# L6205PD-Dual-Breakout-Board-B_00_02.net
KiCad netlist of a schematic drawn in EasyEDA
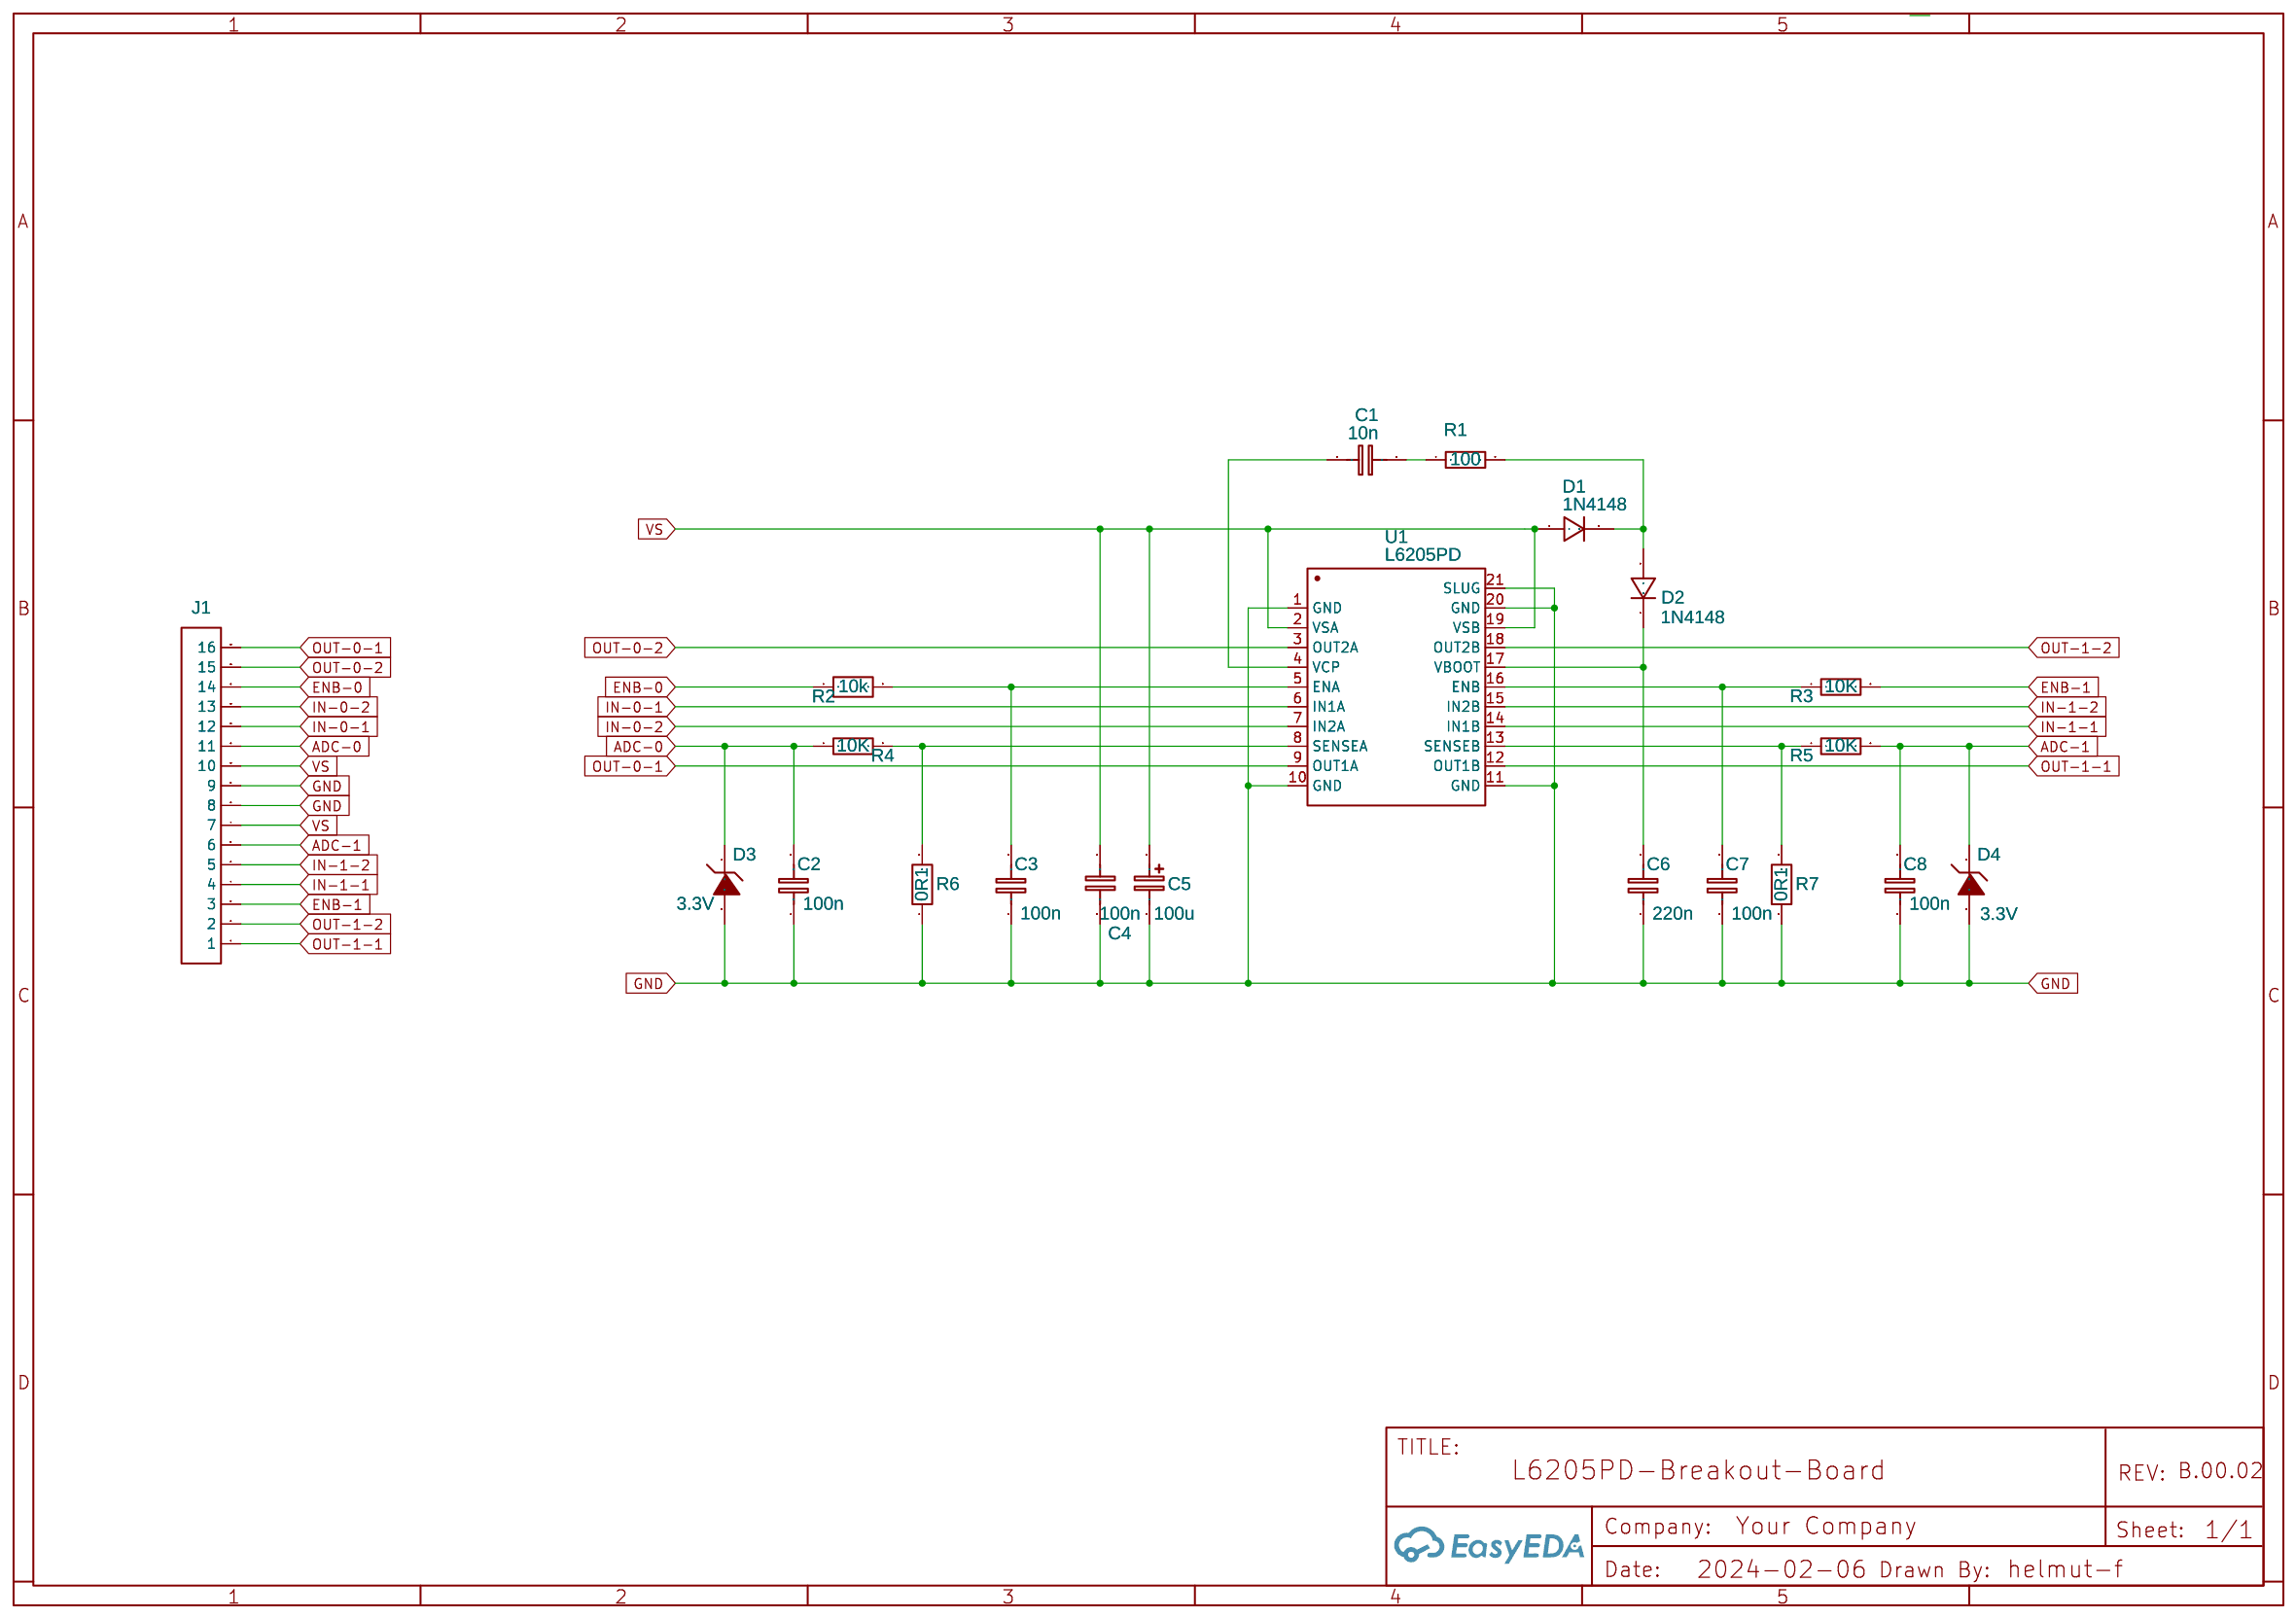
[diagram p0: schematic sheet]

(export (version "E")
  (design (tool "Eeschema 10.0.6"))
  (components
    (comp (ref "C1") (value "10n") (libsource (lib "") (part "C_0603_EU_3")))
    (comp (ref "C2") (value "100n") (libsource (lib "") (part "C_0603_EU")))
    (comp (ref "C3") (value "100n") (libsource (lib "") (part "C_0603_EU_1")))
    (comp (ref "C4") (value "100n") (libsource (lib "") (part "C_0603_EU_2")))
    (comp (ref "C5") (value "100u") (libsource (lib "") (part "CE_SMD_D5.0×H5.5_EU")))
    (comp (ref "C6") (value "220n") (libsource (lib "") (part "C_0603_EU_1")))
    (comp (ref "C7") (value "100n") (libsource (lib "") (part "C_0603_EU_1")))
    (comp (ref "C8") (value "100n") (libsource (lib "") (part "C_0603_EU_1")))
    (comp (ref "D1")
      (value "1N4148")
      (fields (field (name "Manufacturer") "SEMTECH"))
      (libsource (lib "") (part "1N4148"))
    )
    (comp (ref "D2")
      (value "1N4148")
      (fields (field (name "Manufacturer") "SEMTECH"))
      (libsource (lib "") (part "1N4148_1"))
    )
    (comp (ref "D3")
      (value "3.3V")
      (fields (field (name "Manufacturer Part") "Diode Zener") (field (name "Manufacturer") "SEMTECH"))
      (libsource (lib "") (part "Diode Zener"))
    )
    (comp (ref "D4")
      (value "3.3V")
      (fields (field (name "Manufacturer Part") "Diode Zener") (field (name "Manufacturer") "SEMTECH"))
      (libsource (lib "") (part "Diode Zener"))
    )
    (comp (ref "J1") (value "HDR-M-2.54_1x16") (libsource (lib "") (part "HDR-M-2.54_1x16")))
    (comp (ref "R1") (value "100") (libsource (lib "") (part "RESISTOR-AXIAL-0.1")))
    (comp (ref "R2") (value "10k") (libsource (lib "") (part "R_AXIAL-0.3_EU_1")))
    (comp (ref "R3") (value "10K") (libsource (lib "") (part "RESISTOR-AXIAL-0.1")))
    (comp (ref "R4") (value "10K") (libsource (lib "") (part "RESISTOR-AXIAL-0.1")))
    (comp (ref "R5") (value "10K") (libsource (lib "") (part "RESISTOR-AXIAL-0.1")))
    (comp (ref "R6") (value "0R1") (libsource (lib "") (part "R_AXIAL-0.3_EU")))
    (comp (ref "R7") (value "0R1") (libsource (lib "") (part "R_AXIAL-0.3_EU")))
    (comp (ref "U1")
      (value "L6205PD")
      (fields (field (name "Manufacturer Part") "L6205PD013TR") (field (name "Manufacturer") "ST(意法半导体)"))
      (libsource (lib "") (part "L6205PD"))
    )
  )
  (nets
    (net (code "1") (name "ADC-0") (class "Default")
      (node (ref "C2") (pin "2") (pinfunction "2_2") (pintype "unspecified"))
      (node (ref "D3") (pin "1") (pinfunction "C_1") (pintype "unspecified"))
      (node (ref "J1") (pin "11") (pinfunction "11_11") (pintype "unspecified"))
      (node (ref "R4") (pin "1") (pinfunction "1_1") (pintype "input"))
    )
    (net (code "2") (name "ADC-1") (class "Default")
      (node (ref "C8") (pin "2") (pinfunction "2_2") (pintype "unspecified"))
      (node (ref "D4") (pin "1") (pinfunction "C_1") (pintype "unspecified"))
      (node (ref "J1") (pin "6") (pinfunction "6_6") (pintype "unspecified"))
      (node (ref "R5") (pin "2") (pinfunction "2_2") (pintype "input"))
    )
    (net (code "3") (name "ENB-0") (class "Default")
      (node (ref "J1") (pin "14") (pinfunction "14_14") (pintype "unspecified"))
      (node (ref "R2") (pin "1") (pinfunction "1_1") (pintype "unspecified"))
    )
    (net (code "4") (name "ENB-1") (class "Default")
      (node (ref "J1") (pin "3") (pinfunction "3_3") (pintype "unspecified"))
      (node (ref "R3") (pin "2") (pinfunction "2_2") (pintype "input"))
    )
    (net (code "5") (name "GND") (class "Default")
      (node (ref "C2") (pin "1") (pinfunction "1_1") (pintype "unspecified"))
      (node (ref "C3") (pin "1") (pinfunction "1_1") (pintype "unspecified"))
      (node (ref "C4") (pin "2") (pinfunction "2_2") (pintype "unspecified"))
      (node (ref "C5") (pin "2") (pinfunction "2_2") (pintype "unspecified"))
      (node (ref "C6") (pin "1") (pinfunction "1_1") (pintype "unspecified"))
      (node (ref "C7") (pin "1") (pinfunction "1_1") (pintype "unspecified"))
      (node (ref "C8") (pin "1") (pinfunction "1_1") (pintype "unspecified"))
      (node (ref "D3") (pin "2") (pinfunction "A_2") (pintype "unspecified"))
      (node (ref "D4") (pin "2") (pinfunction "A_2") (pintype "unspecified"))
      (node (ref "J1") (pin "8") (pinfunction "8_8") (pintype "unspecified"))
      (node (ref "J1") (pin "9") (pinfunction "9_9") (pintype "unspecified"))
      (node (ref "R6") (pin "1") (pinfunction "1_1") (pintype "unspecified"))
      (node (ref "R7") (pin "1") (pinfunction "1_1") (pintype "unspecified"))
      (node (ref "U1") (pin "1") (pinfunction "GND_1") (pintype "unspecified"))
      (node (ref "U1") (pin "10") (pinfunction "GND_10") (pintype "unspecified"))
      (node (ref "U1") (pin "11") (pinfunction "GND_11") (pintype "unspecified"))
      (node (ref "U1") (pin "20") (pinfunction "GND_20") (pintype "unspecified"))
      (node (ref "U1") (pin "21") (pinfunction "SLUG_21") (pintype "unspecified"))
    )
    (net (code "6") (name "IN-0-1") (class "Default")
      (node (ref "J1") (pin "12") (pinfunction "12_12") (pintype "unspecified"))
      (node (ref "U1") (pin "6") (pinfunction "IN1A_6") (pintype "unspecified"))
    )
    (net (code "7") (name "IN-0-2") (class "Default")
      (node (ref "J1") (pin "13") (pinfunction "13_13") (pintype "unspecified"))
      (node (ref "U1") (pin "7") (pinfunction "IN2A_7") (pintype "unspecified"))
    )
    (net (code "8") (name "IN-1-1") (class "Default")
      (node (ref "J1") (pin "4") (pinfunction "4_4") (pintype "unspecified"))
      (node (ref "U1") (pin "14") (pinfunction "IN1B_14") (pintype "unspecified"))
    )
    (net (code "9") (name "IN-1-2") (class "Default")
      (node (ref "J1") (pin "5") (pinfunction "5_5") (pintype "unspecified"))
      (node (ref "U1") (pin "15") (pinfunction "IN2B_15") (pintype "unspecified"))
    )
    (net (code "10") (name "Net-(C1-Pad2)") (class "Default")
      (node (ref "C1") (pin "2") (pinfunction "2_2") (pintype "unspecified"))
      (node (ref "R1") (pin "1") (pinfunction "1_1") (pintype "input"))
    )
    (net (code "11") (name "Net-(D1-2)") (class "Default")
      (node (ref "D1") (pin "1") (pinfunction "2_1") (pintype "unspecified"))
      (node (ref "D2") (pin "2") (pinfunction "1_2") (pintype "unspecified"))
      (node (ref "R1") (pin "2") (pinfunction "2_2") (pintype "input"))
    )
    (net (code "12") (name "Net-(D2-2)") (class "Default")
      (node (ref "C6") (pin "2") (pinfunction "2_2") (pintype "unspecified"))
      (node (ref "D2") (pin "1") (pinfunction "2_1") (pintype "unspecified"))
      (node (ref "U1") (pin "17") (pinfunction "VBOOT_17") (pintype "unspecified"))
    )
    (net (code "13") (name "Net-(U1-ENA)") (class "Default")
      (node (ref "C3") (pin "2") (pinfunction "2_2") (pintype "unspecified"))
      (node (ref "R2") (pin "2") (pinfunction "2_2") (pintype "unspecified"))
      (node (ref "U1") (pin "5") (pinfunction "ENA_5") (pintype "unspecified"))
    )
    (net (code "14") (name "Net-(U1-ENB)") (class "Default")
      (node (ref "C7") (pin "2") (pinfunction "2_2") (pintype "unspecified"))
      (node (ref "R3") (pin "1") (pinfunction "1_1") (pintype "input"))
      (node (ref "U1") (pin "16") (pinfunction "ENB_16") (pintype "unspecified"))
    )
    (net (code "15") (name "Net-(U1-SENSEA)") (class "Default")
      (node (ref "R4") (pin "2") (pinfunction "2_2") (pintype "input"))
      (node (ref "R6") (pin "2") (pinfunction "2_2") (pintype "unspecified"))
      (node (ref "U1") (pin "8") (pinfunction "SENSEA_8") (pintype "unspecified"))
    )
    (net (code "16") (name "Net-(U1-SENSEB)") (class "Default")
      (node (ref "R5") (pin "1") (pinfunction "1_1") (pintype "input"))
      (node (ref "R7") (pin "2") (pinfunction "2_2") (pintype "unspecified"))
      (node (ref "U1") (pin "13") (pinfunction "SENSEB_13") (pintype "unspecified"))
    )
    (net (code "17") (name "Net-(U1-VCP)") (class "Default")
      (node (ref "C1") (pin "1") (pinfunction "1_1") (pintype "unspecified"))
      (node (ref "U1") (pin "4") (pinfunction "VCP_4") (pintype "unspecified"))
    )
    (net (code "18") (name "OUT-0-1") (class "Default")
      (node (ref "J1") (pin "16") (pinfunction "16_16") (pintype "unspecified"))
      (node (ref "U1") (pin "9") (pinfunction "OUT1A_9") (pintype "unspecified"))
    )
    (net (code "19") (name "OUT-0-2") (class "Default")
      (node (ref "J1") (pin "15") (pinfunction "15_15") (pintype "unspecified"))
      (node (ref "U1") (pin "3") (pinfunction "OUT2A_3") (pintype "unspecified"))
    )
    (net (code "20") (name "OUT-1-1") (class "Default")
      (node (ref "J1") (pin "1") (pinfunction "1_1") (pintype "unspecified"))
      (node (ref "U1") (pin "12") (pinfunction "OUT1B_12") (pintype "unspecified"))
    )
    (net (code "21") (name "OUT-1-2") (class "Default")
      (node (ref "J1") (pin "2") (pinfunction "2_2") (pintype "unspecified"))
      (node (ref "U1") (pin "18") (pinfunction "OUT2B_18") (pintype "unspecified"))
    )
    (net (code "22") (name "VS") (class "Default")
      (node (ref "C4") (pin "1") (pinfunction "1_1") (pintype "unspecified"))
      (node (ref "C5") (pin "1") (pinfunction "1_1") (pintype "unspecified"))
      (node (ref "D1") (pin "2") (pinfunction "1_2") (pintype "unspecified"))
      (node (ref "J1") (pin "10") (pinfunction "10_10") (pintype "unspecified"))
      (node (ref "J1") (pin "7") (pinfunction "7_7") (pintype "unspecified"))
      (node (ref "U1") (pin "19") (pinfunction "VSB_19") (pintype "unspecified"))
      (node (ref "U1") (pin "2") (pinfunction "VSA_2") (pintype "unspecified"))
    )
  )
)
